# W102J.net
KiCad netlist of a schematic drawn in EAGLE
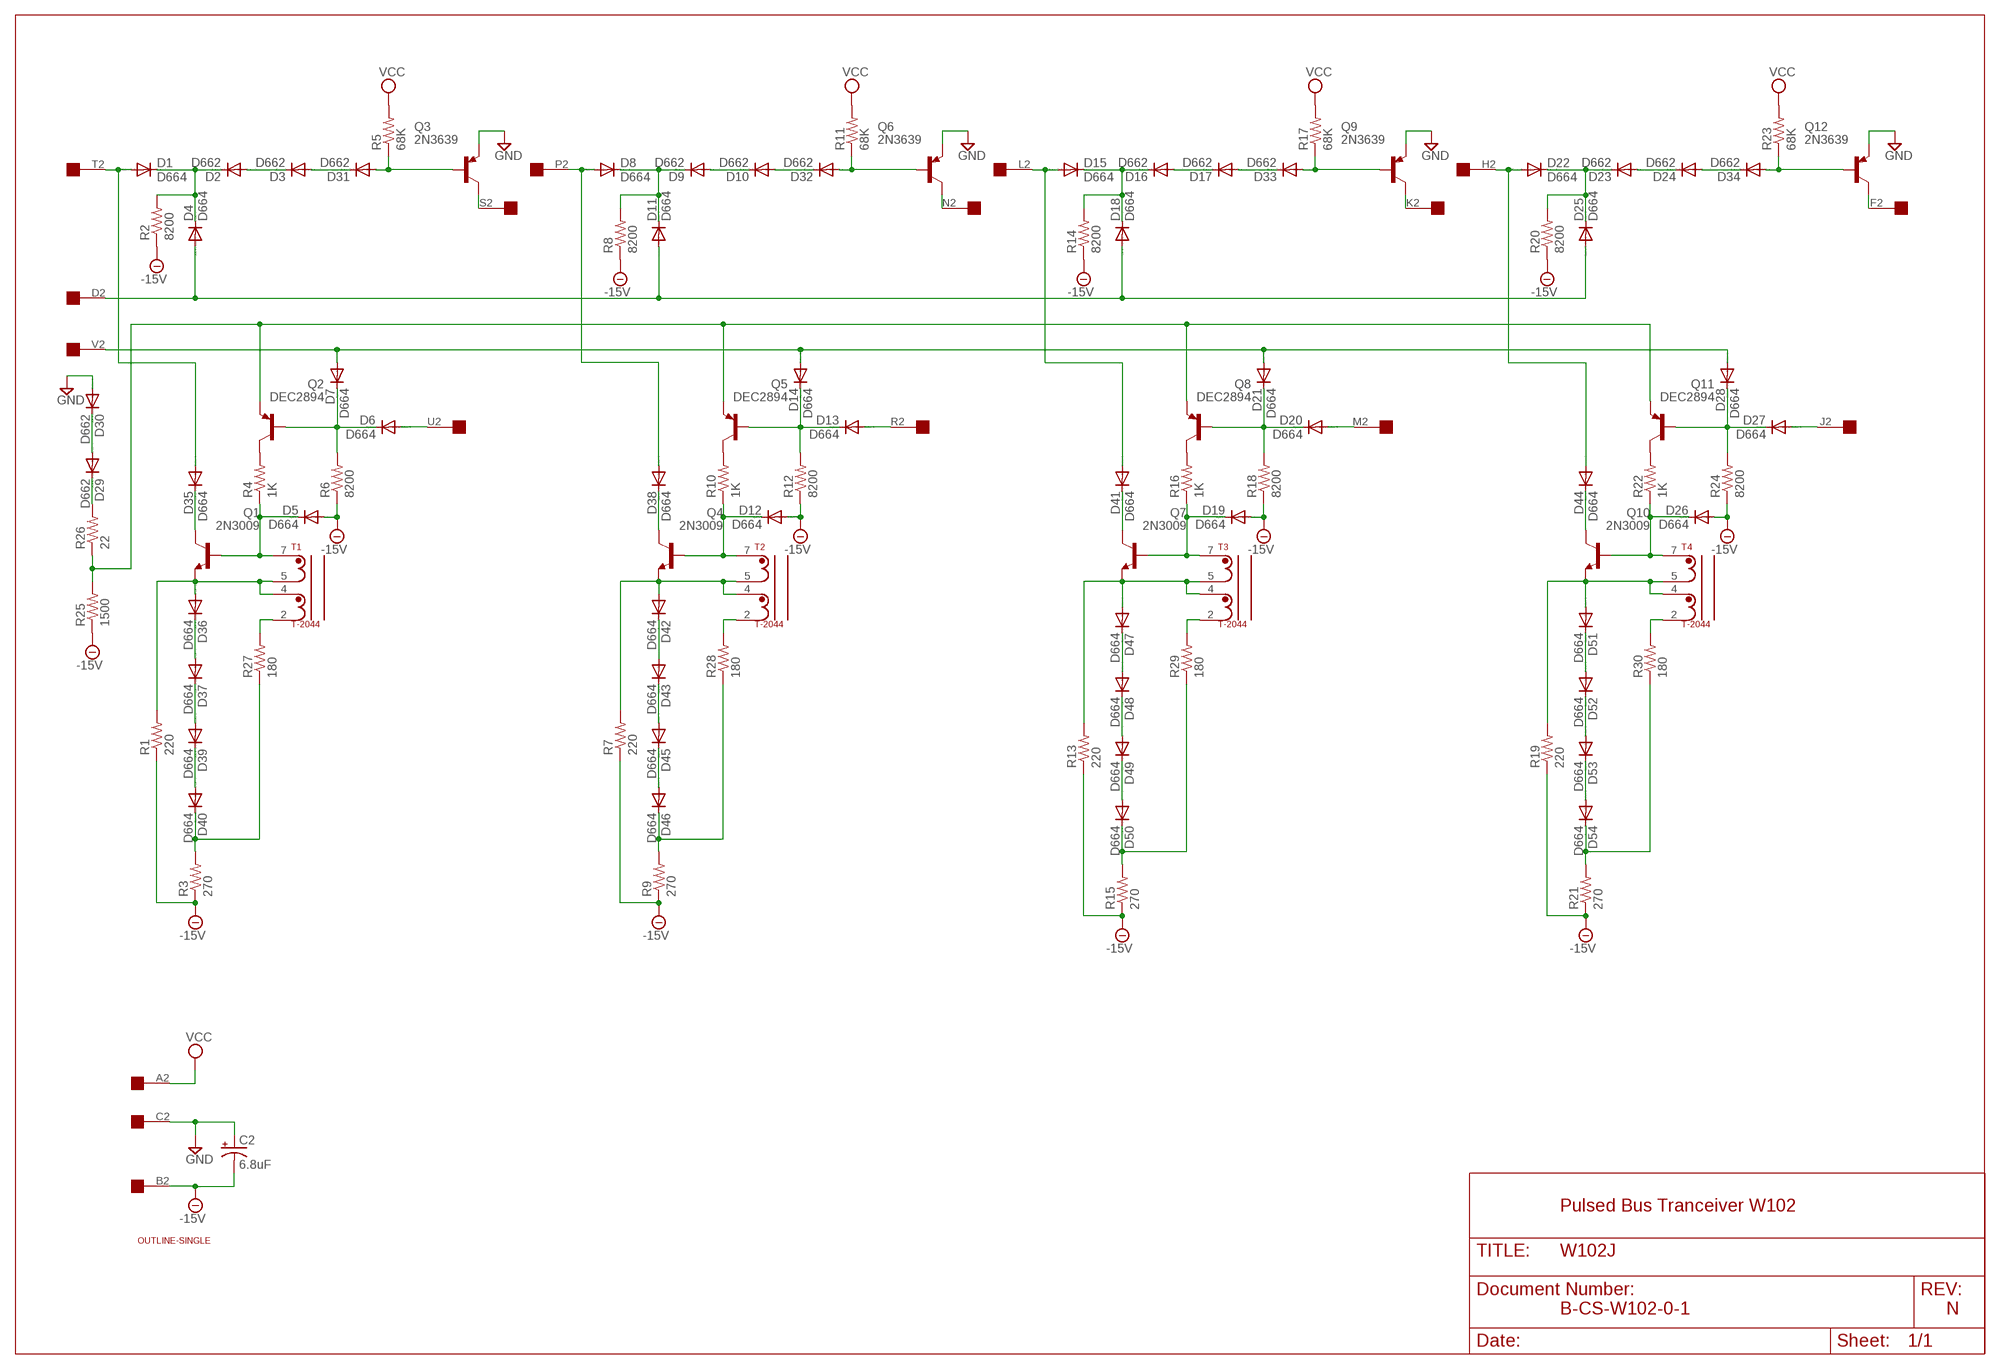
[diagram p0: schematic, sheet 1]

(export (version "E")
  (design (tool "Eeschema 10.0.6"))
  (components
    (comp (ref "C2")
      (value "6.8uF")
      (footprint "eagle-import:E15-5")
      (libsource (lib "eagle-import") (part "CPOL-USE15-5AXIAL"))
    )
    (comp (ref "D1")
      (value "D664")
      (footprint "eagle-import:DO35-10")
      (libsource (lib "eagle-import") (part "DIODE-DO35-10"))
    )
    (comp (ref "D2")
      (value "D662")
      (footprint "eagle-import:DO35-10")
      (libsource (lib "eagle-import") (part "DIODE-DO35-10"))
    )
    (comp (ref "D3")
      (value "D662")
      (footprint "eagle-import:DO35-10")
      (libsource (lib "eagle-import") (part "DIODE-DO35-10"))
    )
    (comp (ref "D4")
      (value "D664")
      (footprint "eagle-import:DO35-10")
      (libsource (lib "eagle-import") (part "DIODE-DO35-10"))
    )
    (comp (ref "D5")
      (value "D664")
      (footprint "eagle-import:DO35-10")
      (libsource (lib "eagle-import") (part "DIODE-DO35-10"))
    )
    (comp (ref "D6")
      (value "D664")
      (footprint "eagle-import:DO35-10")
      (libsource (lib "eagle-import") (part "DIODE-DO35-10"))
    )
    (comp (ref "D7")
      (value "D664")
      (footprint "eagle-import:DO35-10")
      (libsource (lib "eagle-import") (part "DIODE-DO35-10"))
    )
    (comp (ref "D8")
      (value "D664")
      (footprint "eagle-import:DO35-10")
      (libsource (lib "eagle-import") (part "DIODE-DO35-10"))
    )
    (comp (ref "D9")
      (value "D662")
      (footprint "eagle-import:DO35-10")
      (libsource (lib "eagle-import") (part "DIODE-DO35-10"))
    )
    (comp (ref "D10")
      (value "D662")
      (footprint "eagle-import:DO35-10")
      (libsource (lib "eagle-import") (part "DIODE-DO35-10"))
    )
    (comp (ref "D11")
      (value "D664")
      (footprint "eagle-import:DO35-10")
      (libsource (lib "eagle-import") (part "DIODE-DO35-10"))
    )
    (comp (ref "D12")
      (value "D664")
      (footprint "eagle-import:DO35-10")
      (libsource (lib "eagle-import") (part "DIODE-DO35-10"))
    )
    (comp (ref "D13")
      (value "D664")
      (footprint "eagle-import:DO35-10")
      (libsource (lib "eagle-import") (part "DIODE-DO35-10"))
    )
    (comp (ref "D14")
      (value "D664")
      (footprint "eagle-import:DO35-10")
      (libsource (lib "eagle-import") (part "DIODE-DO35-10"))
    )
    (comp (ref "D15")
      (value "D664")
      (footprint "eagle-import:DO35-10")
      (libsource (lib "eagle-import") (part "DIODE-DO35-10"))
    )
    (comp (ref "D16")
      (value "D662")
      (footprint "eagle-import:DO35-10")
      (libsource (lib "eagle-import") (part "DIODE-DO35-10"))
    )
    (comp (ref "D17")
      (value "D662")
      (footprint "eagle-import:DO35-10")
      (libsource (lib "eagle-import") (part "DIODE-DO35-10"))
    )
    (comp (ref "D18")
      (value "D664")
      (footprint "eagle-import:DO35-10")
      (libsource (lib "eagle-import") (part "DIODE-DO35-10"))
    )
    (comp (ref "D19")
      (value "D664")
      (footprint "eagle-import:DO35-10")
      (libsource (lib "eagle-import") (part "DIODE-DO35-10"))
    )
    (comp (ref "D20")
      (value "D664")
      (footprint "eagle-import:DO35-10")
      (libsource (lib "eagle-import") (part "DIODE-DO35-10"))
    )
    (comp (ref "D21")
      (value "D664")
      (footprint "eagle-import:DO35-10")
      (libsource (lib "eagle-import") (part "DIODE-DO35-10"))
    )
    (comp (ref "D22")
      (value "D664")
      (footprint "eagle-import:DO35-10")
      (libsource (lib "eagle-import") (part "DIODE-DO35-10"))
    )
    (comp (ref "D23")
      (value "D662")
      (footprint "eagle-import:DO35-10")
      (libsource (lib "eagle-import") (part "DIODE-DO35-10"))
    )
    (comp (ref "D24")
      (value "D662")
      (footprint "eagle-import:DO35-10")
      (libsource (lib "eagle-import") (part "DIODE-DO35-10"))
    )
    (comp (ref "D25")
      (value "D664")
      (footprint "eagle-import:DO35-10")
      (libsource (lib "eagle-import") (part "DIODE-DO35-10"))
    )
    (comp (ref "D26")
      (value "D664")
      (footprint "eagle-import:DO35-10")
      (libsource (lib "eagle-import") (part "DIODE-DO35-10"))
    )
    (comp (ref "D27")
      (value "D664")
      (footprint "eagle-import:DO35-10")
      (libsource (lib "eagle-import") (part "DIODE-DO35-10"))
    )
    (comp (ref "D28")
      (value "D664")
      (footprint "eagle-import:DO35-10")
      (libsource (lib "eagle-import") (part "DIODE-DO35-10"))
    )
    (comp (ref "D29")
      (value "D662")
      (footprint "eagle-import:DO35-10")
      (libsource (lib "eagle-import") (part "DIODE-DO35-10"))
    )
    (comp (ref "D30")
      (value "D662")
      (footprint "eagle-import:DO35-10")
      (libsource (lib "eagle-import") (part "DIODE-DO35-10"))
    )
    (comp (ref "D31")
      (value "D662")
      (footprint "eagle-import:DO35-10")
      (libsource (lib "eagle-import") (part "DIODE-DO35-10"))
    )
    (comp (ref "D32")
      (value "D662")
      (footprint "eagle-import:DO35-10")
      (libsource (lib "eagle-import") (part "DIODE-DO35-10"))
    )
    (comp (ref "D33")
      (value "D662")
      (footprint "eagle-import:DO35-10")
      (libsource (lib "eagle-import") (part "DIODE-DO35-10"))
    )
    (comp (ref "D34")
      (value "D662")
      (footprint "eagle-import:DO35-10")
      (libsource (lib "eagle-import") (part "DIODE-DO35-10"))
    )
    (comp (ref "D35")
      (value "D664")
      (footprint "eagle-import:DO35-10")
      (libsource (lib "eagle-import") (part "DIODE-DO35-10"))
    )
    (comp (ref "D36")
      (value "D664")
      (footprint "eagle-import:DO35-10")
      (libsource (lib "eagle-import") (part "DIODE-DO35-10"))
    )
    (comp (ref "D37")
      (value "D664")
      (footprint "eagle-import:DO35-10")
      (libsource (lib "eagle-import") (part "DIODE-DO35-10"))
    )
    (comp (ref "D38")
      (value "D664")
      (footprint "eagle-import:DO35-10")
      (libsource (lib "eagle-import") (part "DIODE-DO35-10"))
    )
    (comp (ref "D39")
      (value "D664")
      (footprint "eagle-import:DO35-10")
      (libsource (lib "eagle-import") (part "DIODE-DO35-10"))
    )
    (comp (ref "D40")
      (value "D664")
      (footprint "eagle-import:DO35-10")
      (libsource (lib "eagle-import") (part "DIODE-DO35-10"))
    )
    (comp (ref "D41")
      (value "D664")
      (footprint "eagle-import:DO35-10")
      (libsource (lib "eagle-import") (part "DIODE-DO35-10"))
    )
    (comp (ref "D42")
      (value "D664")
      (footprint "eagle-import:DO35-10")
      (libsource (lib "eagle-import") (part "DIODE-DO35-10"))
    )
    (comp (ref "D43")
      (value "D664")
      (footprint "eagle-import:DO35-10")
      (libsource (lib "eagle-import") (part "DIODE-DO35-10"))
    )
    (comp (ref "D44")
      (value "D664")
      (footprint "eagle-import:DO35-10")
      (libsource (lib "eagle-import") (part "DIODE-DO35-10"))
    )
    (comp (ref "D45")
      (value "D664")
      (footprint "eagle-import:DO35-10")
      (libsource (lib "eagle-import") (part "DIODE-DO35-10"))
    )
    (comp (ref "D46")
      (value "D664")
      (footprint "eagle-import:DO35-10")
      (libsource (lib "eagle-import") (part "DIODE-DO35-10"))
    )
    (comp (ref "D47")
      (value "D664")
      (footprint "eagle-import:DO35-10")
      (libsource (lib "eagle-import") (part "DIODE-DO35-10"))
    )
    (comp (ref "D48")
      (value "D664")
      (footprint "eagle-import:DO35-10")
      (libsource (lib "eagle-import") (part "DIODE-DO35-10"))
    )
    (comp (ref "D49")
      (value "D664")
      (footprint "eagle-import:DO35-10")
      (libsource (lib "eagle-import") (part "DIODE-DO35-10"))
    )
    (comp (ref "D50")
      (value "D664")
      (footprint "eagle-import:DO35-10")
      (libsource (lib "eagle-import") (part "DIODE-DO35-10"))
    )
    (comp (ref "D51")
      (value "D664")
      (footprint "eagle-import:DO35-10")
      (libsource (lib "eagle-import") (part "DIODE-DO35-10"))
    )
    (comp (ref "D52")
      (value "D664")
      (footprint "eagle-import:DO35-10")
      (libsource (lib "eagle-import") (part "DIODE-DO35-10"))
    )
    (comp (ref "D53")
      (value "D664")
      (footprint "eagle-import:DO35-10")
      (libsource (lib "eagle-import") (part "DIODE-DO35-10"))
    )
    (comp (ref "D54")
      (value "D664")
      (footprint "eagle-import:DO35-10")
      (libsource (lib "eagle-import") (part "DIODE-DO35-10"))
    )
    (comp (ref "Q1")
      (value "2N3009")
      (footprint "eagle-import:TO5")
      (libsource (lib "eagle-import") (part "-NPN-TO5"))
    )
    (comp (ref "Q2")
      (value "DEC2894")
      (footprint "eagle-import:TO5")
      (libsource (lib "eagle-import") (part "-PNP-TO5"))
    )
    (comp (ref "Q3")
      (value "2N3639")
      (footprint "eagle-import:TO5")
      (libsource (lib "eagle-import") (part "-PNP-TO5"))
    )
    (comp (ref "Q4")
      (value "2N3009")
      (footprint "eagle-import:TO5")
      (libsource (lib "eagle-import") (part "-NPN-TO5"))
    )
    (comp (ref "Q5")
      (value "DEC2894")
      (footprint "eagle-import:TO5")
      (libsource (lib "eagle-import") (part "-PNP-TO5"))
    )
    (comp (ref "Q6")
      (value "2N3639")
      (footprint "eagle-import:TO5")
      (libsource (lib "eagle-import") (part "-PNP-TO5"))
    )
    (comp (ref "Q7")
      (value "2N3009")
      (footprint "eagle-import:TO5")
      (libsource (lib "eagle-import") (part "-NPN-TO5"))
    )
    (comp (ref "Q8")
      (value "DEC2894")
      (footprint "eagle-import:TO5")
      (libsource (lib "eagle-import") (part "-PNP-TO5"))
    )
    (comp (ref "Q9")
      (value "2N3639")
      (footprint "eagle-import:TO5")
      (libsource (lib "eagle-import") (part "-PNP-TO5"))
    )
    (comp (ref "Q10")
      (value "2N3009")
      (footprint "eagle-import:TO5")
      (libsource (lib "eagle-import") (part "-NPN-TO5"))
    )
    (comp (ref "Q11")
      (value "DEC2894")
      (footprint "eagle-import:TO5")
      (libsource (lib "eagle-import") (part "-PNP-TO5"))
    )
    (comp (ref "Q12")
      (value "2N3639")
      (footprint "eagle-import:TO5")
      (libsource (lib "eagle-import") (part "-PNP-TO5"))
    )
    (comp (ref "R1")
      (value "220")
      (footprint "eagle-import:0207_10")
      (libsource (lib "eagle-import") (part "R-US_0207/10"))
    )
    (comp (ref "R2")
      (value "8200")
      (footprint "eagle-import:0207_10")
      (libsource (lib "eagle-import") (part "R-US_0207/10"))
    )
    (comp (ref "R3")
      (value "270")
      (footprint "eagle-import:0207_10")
      (libsource (lib "eagle-import") (part "R-US_0207/10"))
    )
    (comp (ref "R4")
      (value "1K")
      (footprint "eagle-import:0207_10")
      (libsource (lib "eagle-import") (part "R-US_0207/10"))
    )
    (comp (ref "R5")
      (value "68K")
      (footprint "eagle-import:0207_10")
      (libsource (lib "eagle-import") (part "R-US_0207/10"))
    )
    (comp (ref "R6")
      (value "8200")
      (footprint "eagle-import:0207_10")
      (libsource (lib "eagle-import") (part "R-US_0207/10"))
    )
    (comp (ref "R7")
      (value "220")
      (footprint "eagle-import:0207_10")
      (libsource (lib "eagle-import") (part "R-US_0207/10"))
    )
    (comp (ref "R8")
      (value "8200")
      (footprint "eagle-import:0207_10")
      (libsource (lib "eagle-import") (part "R-US_0207/10"))
    )
    (comp (ref "R9")
      (value "270")
      (footprint "eagle-import:0207_10")
      (libsource (lib "eagle-import") (part "R-US_0207/10"))
    )
    (comp (ref "R10")
      (value "1K")
      (footprint "eagle-import:0207_10")
      (libsource (lib "eagle-import") (part "R-US_0207/10"))
    )
    (comp (ref "R11")
      (value "68K")
      (footprint "eagle-import:0207_10")
      (libsource (lib "eagle-import") (part "R-US_0207/10"))
    )
    (comp (ref "R12")
      (value "8200")
      (footprint "eagle-import:0207_10")
      (libsource (lib "eagle-import") (part "R-US_0207/10"))
    )
    (comp (ref "R13")
      (value "220")
      (footprint "eagle-import:0207_10")
      (libsource (lib "eagle-import") (part "R-US_0207/10"))
    )
    (comp (ref "R14")
      (value "8200")
      (footprint "eagle-import:0207_10")
      (libsource (lib "eagle-import") (part "R-US_0207/10"))
    )
    (comp (ref "R15")
      (value "270")
      (footprint "eagle-import:0207_10")
      (libsource (lib "eagle-import") (part "R-US_0207/10"))
    )
    (comp (ref "R16")
      (value "1K")
      (footprint "eagle-import:0207_10")
      (libsource (lib "eagle-import") (part "R-US_0207/10"))
    )
    (comp (ref "R17")
      (value "68K")
      (footprint "eagle-import:0207_10")
      (libsource (lib "eagle-import") (part "R-US_0207/10"))
    )
    (comp (ref "R18")
      (value "8200")
      (footprint "eagle-import:0207_10")
      (libsource (lib "eagle-import") (part "R-US_0207/10"))
    )
    (comp (ref "R19")
      (value "220")
      (footprint "eagle-import:0207_10")
      (libsource (lib "eagle-import") (part "R-US_0207/10"))
    )
    (comp (ref "R20")
      (value "8200")
      (footprint "eagle-import:0207_10")
      (libsource (lib "eagle-import") (part "R-US_0207/10"))
    )
    (comp (ref "R21")
      (value "270")
      (footprint "eagle-import:0207_10")
      (libsource (lib "eagle-import") (part "R-US_0207/10"))
    )
    (comp (ref "R22")
      (value "1K")
      (footprint "eagle-import:0207_10")
      (libsource (lib "eagle-import") (part "R-US_0207/10"))
    )
    (comp (ref "R23")
      (value "68K")
      (footprint "eagle-import:0207_10")
      (libsource (lib "eagle-import") (part "R-US_0207/10"))
    )
    (comp (ref "R24")
      (value "8200")
      (footprint "eagle-import:0207_10")
      (libsource (lib "eagle-import") (part "R-US_0207/10"))
    )
    (comp (ref "R25")
      (value "1500")
      (footprint "eagle-import:0207_10")
      (libsource (lib "eagle-import") (part "R-US_0207/10"))
    )
    (comp (ref "R26")
      (value "22")
      (footprint "eagle-import:0207_10")
      (libsource (lib "eagle-import") (part "R-US_0207/10"))
    )
    (comp (ref "R27")
      (value "180")
      (footprint "eagle-import:0207_10")
      (libsource (lib "eagle-import") (part "R-US_0207/10"))
    )
    (comp (ref "R28")
      (value "180")
      (footprint "eagle-import:0207_10")
      (libsource (lib "eagle-import") (part "R-US_0207/10"))
    )
    (comp (ref "R29")
      (value "180")
      (footprint "eagle-import:0207_10")
      (libsource (lib "eagle-import") (part "R-US_0207/10"))
    )
    (comp (ref "R30")
      (value "180")
      (footprint "eagle-import:0207_10")
      (libsource (lib "eagle-import") (part "R-US_0207/10"))
    )
    (comp (ref "T1")
      (value "T-2044")
      (footprint "eagle-import:TRANSFORMER")
      (libsource (lib "eagle-import") (part "T-2044"))
    )
    (comp (ref "T2")
      (value "T-2044")
      (footprint "eagle-import:TRANSFORMER")
      (libsource (lib "eagle-import") (part "T-2044"))
    )
    (comp (ref "T3")
      (value "T-2044")
      (footprint "eagle-import:TRANSFORMER")
      (libsource (lib "eagle-import") (part "T-2044"))
    )
    (comp (ref "T4")
      (value "T-2044")
      (footprint "eagle-import:TRANSFORMER")
      (libsource (lib "eagle-import") (part "T-2044"))
    )
    (comp (ref "U$1")
      (value "OUTLINE-SINGLE")
      (footprint "eagle-import:SINGLE")
      (libsource (lib "eagle-import") (part "OUTLINE-SINGLE"))
    )
    (comp (ref "U$2")
      (value "EDGE-1")
      (footprint "eagle-import:EDGE-CON1")
      (libsource (lib "eagle-import") (part "EDGE-1"))
    )
  )
  (nets
    (net (code "1") (name "-15V") (class "Default")
      (node (ref "C2") (pin "-") (pinfunction "-_-") (pintype "passive"))
      (node (ref "D12") (pin "A") (pinfunction "A_A") (pintype "passive"))
      (node (ref "D19") (pin "A") (pinfunction "A_A") (pintype "passive"))
      (node (ref "D26") (pin "A") (pinfunction "A_A") (pintype "passive"))
      (node (ref "D5") (pin "A") (pinfunction "A_A") (pintype "passive"))
      (node (ref "R1") (pin "1") (pinfunction "1_1") (pintype "passive"))
      (node (ref "R12") (pin "1") (pinfunction "1_1") (pintype "passive"))
      (node (ref "R13") (pin "1") (pinfunction "1_1") (pintype "passive"))
      (node (ref "R14") (pin "1") (pinfunction "1_1") (pintype "passive"))
      (node (ref "R15") (pin "1") (pinfunction "1_1") (pintype "passive"))
      (node (ref "R18") (pin "1") (pinfunction "1_1") (pintype "passive"))
      (node (ref "R19") (pin "1") (pinfunction "1_1") (pintype "passive"))
      (node (ref "R2") (pin "1") (pinfunction "1_1") (pintype "passive"))
      (node (ref "R20") (pin "1") (pinfunction "1_1") (pintype "passive"))
      (node (ref "R21") (pin "1") (pinfunction "1_1") (pintype "passive"))
      (node (ref "R24") (pin "1") (pinfunction "1_1") (pintype "passive"))
      (node (ref "R25") (pin "1") (pinfunction "1_1") (pintype "passive"))
      (node (ref "R3") (pin "1") (pinfunction "1_1") (pintype "passive"))
      (node (ref "R6") (pin "1") (pinfunction "1_1") (pintype "passive"))
      (node (ref "R7") (pin "1") (pinfunction "1_1") (pintype "passive"))
      (node (ref "R8") (pin "1") (pinfunction "1_1") (pintype "passive"))
      (node (ref "R9") (pin "1") (pinfunction "1_1") (pintype "passive"))
      (node (ref "U$2") (pin "B2") (pinfunction "1_B2") (pintype "bidirectional"))
    )
    (net (code "2") (name "GND") (class "Default")
      (node (ref "C2") (pin "+") (pinfunction "+_+") (pintype "passive"))
      (node (ref "D30") (pin "A") (pinfunction "A_A") (pintype "passive"))
      (node (ref "Q12") (pin "1") (pinfunction "E_1") (pintype "passive"))
      (node (ref "Q3") (pin "1") (pinfunction "E_1") (pintype "passive"))
      (node (ref "Q6") (pin "1") (pinfunction "E_1") (pintype "passive"))
      (node (ref "Q9") (pin "1") (pinfunction "E_1") (pintype "passive"))
      (node (ref "U$2") (pin "C2") (pinfunction "1_C2") (pintype "bidirectional"))
    )
    (net (code "3") (name "Net-(D1-PadC)") (class "Default")
      (node (ref "D1") (pin "C") (pinfunction "C_C") (pintype "passive"))
      (node (ref "D2") (pin "C") (pinfunction "C_C") (pintype "passive"))
      (node (ref "D4") (pin "C") (pinfunction "C_C") (pintype "passive"))
      (node (ref "R2") (pin "2") (pinfunction "2_2") (pintype "passive"))
    )
    (net (code "4") (name "Net-(D2-PadA)") (class "Default")
      (node (ref "D2") (pin "A") (pinfunction "A_A") (pintype "passive"))
      (node (ref "D3") (pin "C") (pinfunction "C_C") (pintype "passive"))
    )
    (net (code "5") (name "Net-(D3-PadA)") (class "Default")
      (node (ref "D3") (pin "A") (pinfunction "A_A") (pintype "passive"))
      (node (ref "D31") (pin "C") (pinfunction "C_C") (pintype "passive"))
    )
    (net (code "6") (name "Net-(D10-PadA)") (class "Default")
      (node (ref "D10") (pin "A") (pinfunction "A_A") (pintype "passive"))
      (node (ref "D32") (pin "C") (pinfunction "C_C") (pintype "passive"))
    )
    (net (code "7") (name "Net-(D10-PadC)") (class "Default")
      (node (ref "D10") (pin "C") (pinfunction "C_C") (pintype "passive"))
      (node (ref "D9") (pin "A") (pinfunction "A_A") (pintype "passive"))
    )
    (net (code "8") (name "Net-(D11-PadC)") (class "Default")
      (node (ref "D11") (pin "C") (pinfunction "C_C") (pintype "passive"))
      (node (ref "D8") (pin "C") (pinfunction "C_C") (pintype "passive"))
      (node (ref "D9") (pin "C") (pinfunction "C_C") (pintype "passive"))
      (node (ref "R8") (pin "2") (pinfunction "2_2") (pintype "passive"))
    )
    (net (code "9") (name "Net-(D15-PadC)") (class "Default")
      (node (ref "D15") (pin "C") (pinfunction "C_C") (pintype "passive"))
      (node (ref "D16") (pin "C") (pinfunction "C_C") (pintype "passive"))
      (node (ref "D18") (pin "C") (pinfunction "C_C") (pintype "passive"))
      (node (ref "R14") (pin "2") (pinfunction "2_2") (pintype "passive"))
    )
    (net (code "10") (name "Net-(D16-PadA)") (class "Default")
      (node (ref "D16") (pin "A") (pinfunction "A_A") (pintype "passive"))
      (node (ref "D17") (pin "C") (pinfunction "C_C") (pintype "passive"))
    )
    (net (code "11") (name "Net-(D17-PadA)") (class "Default")
      (node (ref "D17") (pin "A") (pinfunction "A_A") (pintype "passive"))
      (node (ref "D33") (pin "C") (pinfunction "C_C") (pintype "passive"))
    )
    (net (code "12") (name "Net-(D22-PadC)") (class "Default")
      (node (ref "D22") (pin "C") (pinfunction "C_C") (pintype "passive"))
      (node (ref "D23") (pin "C") (pinfunction "C_C") (pintype "passive"))
      (node (ref "D25") (pin "C") (pinfunction "C_C") (pintype "passive"))
      (node (ref "R20") (pin "2") (pinfunction "2_2") (pintype "passive"))
    )
    (net (code "13") (name "Net-(D23-PadA)") (class "Default")
      (node (ref "D23") (pin "A") (pinfunction "A_A") (pintype "passive"))
      (node (ref "D24") (pin "C") (pinfunction "C_C") (pintype "passive"))
    )
    (net (code "14") (name "Net-(D24-PadA)") (class "Default")
      (node (ref "D24") (pin "A") (pinfunction "A_A") (pintype "passive"))
      (node (ref "D34") (pin "C") (pinfunction "C_C") (pintype "passive"))
    )
    (net (code "15") (name "Net-(D29-PadA)") (class "Default")
      (node (ref "D29") (pin "A") (pinfunction "A_A") (pintype "passive"))
      (node (ref "D30") (pin "C") (pinfunction "C_C") (pintype "passive"))
    )
    (net (code "16") (name "Net-(D29-PadC)") (class "Default")
      (node (ref "D29") (pin "C") (pinfunction "C_C") (pintype "passive"))
      (node (ref "R26") (pin "2") (pinfunction "2_2") (pintype "passive"))
    )
    (net (code "17") (name "Net-(D36-PadC)") (class "Default")
      (node (ref "D36") (pin "C") (pinfunction "C_C") (pintype "passive"))
      (node (ref "D37") (pin "A") (pinfunction "A_A") (pintype "passive"))
    )
    (net (code "18") (name "Net-(D37-PadC)") (class "Default")
      (node (ref "D37") (pin "C") (pinfunction "C_C") (pintype "passive"))
      (node (ref "D39") (pin "A") (pinfunction "A_A") (pintype "passive"))
    )
    (net (code "19") (name "Net-(D39-PadC)") (class "Default")
      (node (ref "D39") (pin "C") (pinfunction "C_C") (pintype "passive"))
      (node (ref "D40") (pin "A") (pinfunction "A_A") (pintype "passive"))
    )
    (net (code "20") (name "Net-(D40-PadC)") (class "Default")
      (node (ref "D40") (pin "C") (pinfunction "C_C") (pintype "passive"))
      (node (ref "R27") (pin "1") (pinfunction "1_1") (pintype "passive"))
      (node (ref "R3") (pin "2") (pinfunction "2_2") (pintype "passive"))
    )
    (net (code "21") (name "Net-(D42-PadC)") (class "Default")
      (node (ref "D42") (pin "C") (pinfunction "C_C") (pintype "passive"))
      (node (ref "D43") (pin "A") (pinfunction "A_A") (pintype "passive"))
    )
    (net (code "22") (name "Net-(D43-PadC)") (class "Default")
      (node (ref "D43") (pin "C") (pinfunction "C_C") (pintype "passive"))
      (node (ref "D45") (pin "A") (pinfunction "A_A") (pintype "passive"))
    )
    (net (code "23") (name "Net-(D45-PadC)") (class "Default")
      (node (ref "D45") (pin "C") (pinfunction "C_C") (pintype "passive"))
      (node (ref "D46") (pin "A") (pinfunction "A_A") (pintype "passive"))
    )
    (net (code "24") (name "Net-(D46-PadC)") (class "Default")
      (node (ref "D46") (pin "C") (pinfunction "C_C") (pintype "passive"))
      (node (ref "R28") (pin "1") (pinfunction "1_1") (pintype "passive"))
      (node (ref "R9") (pin "2") (pinfunction "2_2") (pintype "passive"))
    )
    (net (code "25") (name "Net-(D47-PadC)") (class "Default")
      (node (ref "D47") (pin "C") (pinfunction "C_C") (pintype "passive"))
      (node (ref "D48") (pin "A") (pinfunction "A_A") (pintype "passive"))
    )
    (net (code "26") (name "Net-(D48-PadC)") (class "Default")
      (node (ref "D48") (pin "C") (pinfunction "C_C") (pintype "passive"))
      (node (ref "D49") (pin "A") (pinfunction "A_A") (pintype "passive"))
    )
    (net (code "27") (name "Net-(D49-PadC)") (class "Default")
      (node (ref "D49") (pin "C") (pinfunction "C_C") (pintype "passive"))
      (node (ref "D50") (pin "A") (pinfunction "A_A") (pintype "passive"))
    )
    (net (code "28") (name "Net-(D50-PadC)") (class "Default")
      (node (ref "D50") (pin "C") (pinfunction "C_C") (pintype "passive"))
      (node (ref "R15") (pin "2") (pinfunction "2_2") (pintype "passive"))
      (node (ref "R29") (pin "1") (pinfunction "1_1") (pintype "passive"))
    )
    (net (code "29") (name "Net-(D51-PadC)") (class "Default")
      (node (ref "D51") (pin "C") (pinfunction "C_C") (pintype "passive"))
      (node (ref "D52") (pin "A") (pinfunction "A_A") (pintype "passive"))
    )
    (net (code "30") (name "Net-(D52-PadC)") (class "Default")
      (node (ref "D52") (pin "C") (pinfunction "C_C") (pintype "passive"))
      (node (ref "D53") (pin "A") (pinfunction "A_A") (pintype "passive"))
    )
    (net (code "31") (name "Net-(D53-PadC)") (class "Default")
      (node (ref "D53") (pin "C") (pinfunction "C_C") (pintype "passive"))
      (node (ref "D54") (pin "A") (pinfunction "A_A") (pintype "passive"))
    )
    (net (code "32") (name "Net-(D54-PadC)") (class "Default")
      (node (ref "D54") (pin "C") (pinfunction "C_C") (pintype "passive"))
      (node (ref "R21") (pin "2") (pinfunction "2_2") (pintype "passive"))
      (node (ref "R30") (pin "1") (pinfunction "1_1") (pintype "passive"))
    )
    (net (code "33") (name "Net-(Q1-B)") (class "Default")
      (node (ref "D5") (pin "C") (pinfunction "C_C") (pintype "passive"))
      (node (ref "Q1") (pin "2") (pinfunction "B_2") (pintype "passive"))
      (node (ref "R4") (pin "1") (pinfunction "1_1") (pintype "passive"))
      (node (ref "T1") (pin "7") (pinfunction "2_7") (pintype "passive"))
    )
    (net (code "34") (name "Net-(Q1-C)") (class "Default")
      (node (ref "D35") (pin "C") (pinfunction "C_C") (pintype "passive"))
      (node (ref "Q1") (pin "3") (pinfunction "C_3") (pintype "passive"))
    )
    (net (code "35") (name "Net-(Q1-E)") (class "Default")
      (node (ref "D36") (pin "A") (pinfunction "A_A") (pintype "passive"))
      (node (ref "Q1") (pin "1") (pinfunction "E_1") (pintype "passive"))
      (node (ref "R1") (pin "2") (pinfunction "2_2") (pintype "passive"))
      (node (ref "T1") (pin "4") (pinfunction "1_4") (pintype "passive"))
      (node (ref "T1") (pin "5") (pinfunction "5_5") (pintype "passive"))
    )
    (net (code "36") (name "Net-(Q2-B)") (class "Default")
      (node (ref "D6") (pin "C") (pinfunction "C_C") (pintype "passive"))
      (node (ref "D7") (pin "C") (pinfunction "C_C") (pintype "passive"))
      (node (ref "Q2") (pin "2") (pinfunction "B_2") (pintype "passive"))
      (node (ref "R6") (pin "2") (pinfunction "2_2") (pintype "passive"))
    )
    (net (code "37") (name "Net-(Q2-C)") (class "Default")
      (node (ref "Q2") (pin "3") (pinfunction "C_3") (pintype "passive"))
      (node (ref "R4") (pin "2") (pinfunction "2_2") (pintype "passive"))
    )
    (net (code "38") (name "Net-(Q3-B)") (class "Default")
      (node (ref "D31") (pin "A") (pinfunction "A_A") (pintype "passive"))
      (node (ref "Q3") (pin "2") (pinfunction "B_2") (pintype "passive"))
      (node (ref "R5") (pin "1") (pinfunction "1_1") (pintype "passive"))
    )
    (net (code "39") (name "Net-(Q3-C)") (class "Default")
      (node (ref "Q3") (pin "3") (pinfunction "C_3") (pintype "passive"))
      (node (ref "U$2") (pin "S2") (pinfunction "1_S2") (pintype "bidirectional"))
    )
    (net (code "40") (name "Net-(Q4-B)") (class "Default")
      (node (ref "D12") (pin "C") (pinfunction "C_C") (pintype "passive"))
      (node (ref "Q4") (pin "2") (pinfunction "B_2") (pintype "passive"))
      (node (ref "R10") (pin "1") (pinfunction "1_1") (pintype "passive"))
      (node (ref "T2") (pin "7") (pinfunction "2_7") (pintype "passive"))
    )
    (net (code "41") (name "Net-(Q4-C)") (class "Default")
      (node (ref "D38") (pin "C") (pinfunction "C_C") (pintype "passive"))
      (node (ref "Q4") (pin "3") (pinfunction "C_3") (pintype "passive"))
    )
    (net (code "42") (name "Net-(Q4-E)") (class "Default")
      (node (ref "D42") (pin "A") (pinfunction "A_A") (pintype "passive"))
      (node (ref "Q4") (pin "1") (pinfunction "E_1") (pintype "passive"))
      (node (ref "R7") (pin "2") (pinfunction "2_2") (pintype "passive"))
      (node (ref "T2") (pin "4") (pinfunction "1_4") (pintype "passive"))
      (node (ref "T2") (pin "5") (pinfunction "5_5") (pintype "passive"))
    )
    (net (code "43") (name "Net-(Q5-B)") (class "Default")
      (node (ref "D13") (pin "C") (pinfunction "C_C") (pintype "passive"))
      (node (ref "D14") (pin "C") (pinfunction "C_C") (pintype "passive"))
      (node (ref "Q5") (pin "2") (pinfunction "B_2") (pintype "passive"))
      (node (ref "R12") (pin "2") (pinfunction "2_2") (pintype "passive"))
    )
    (net (code "44") (name "Net-(Q5-C)") (class "Default")
      (node (ref "Q5") (pin "3") (pinfunction "C_3") (pintype "passive"))
      (node (ref "R10") (pin "2") (pinfunction "2_2") (pintype "passive"))
    )
    (net (code "45") (name "Net-(Q6-B)") (class "Default")
      (node (ref "D32") (pin "A") (pinfunction "A_A") (pintype "passive"))
      (node (ref "Q6") (pin "2") (pinfunction "B_2") (pintype "passive"))
      (node (ref "R11") (pin "1") (pinfunction "1_1") (pintype "passive"))
    )
    (net (code "46") (name "Net-(Q6-C)") (class "Default")
      (node (ref "Q6") (pin "3") (pinfunction "C_3") (pintype "passive"))
      (node (ref "U$2") (pin "N2") (pinfunction "1_N2") (pintype "bidirectional"))
    )
    (net (code "47") (name "Net-(Q7-B)") (class "Default")
      (node (ref "D19") (pin "C") (pinfunction "C_C") (pintype "passive"))
      (node (ref "Q7") (pin "2") (pinfunction "B_2") (pintype "passive"))
      (node (ref "R16") (pin "1") (pinfunction "1_1") (pintype "passive"))
      (node (ref "T3") (pin "7") (pinfunction "2_7") (pintype "passive"))
    )
    (net (code "48") (name "Net-(Q7-C)") (class "Default")
      (node (ref "D41") (pin "C") (pinfunction "C_C") (pintype "passive"))
      (node (ref "Q7") (pin "3") (pinfunction "C_3") (pintype "passive"))
    )
    (net (code "49") (name "Net-(Q7-E)") (class "Default")
      (node (ref "D47") (pin "A") (pinfunction "A_A") (pintype "passive"))
      (node (ref "Q7") (pin "1") (pinfunction "E_1") (pintype "passive"))
      (node (ref "R13") (pin "2") (pinfunction "2_2") (pintype "passive"))
      (node (ref "T3") (pin "4") (pinfunction "1_4") (pintype "passive"))
      (node (ref "T3") (pin "5") (pinfunction "5_5") (pintype "passive"))
    )
    (net (code "50") (name "Net-(Q8-B)") (class "Default")
      (node (ref "D20") (pin "C") (pinfunction "C_C") (pintype "passive"))
      (node (ref "D21") (pin "C") (pinfunction "C_C") (pintype "passive"))
      (node (ref "Q8") (pin "2") (pinfunction "B_2") (pintype "passive"))
      (node (ref "R18") (pin "2") (pinfunction "2_2") (pintype "passive"))
    )
    (net (code "51") (name "Net-(Q8-C)") (class "Default")
      (node (ref "Q8") (pin "3") (pinfunction "C_3") (pintype "passive"))
      (node (ref "R16") (pin "2") (pinfunction "2_2") (pintype "passive"))
    )
    (net (code "52") (name "Net-(Q9-B)") (class "Default")
      (node (ref "D33") (pin "A") (pinfunction "A_A") (pintype "passive"))
      (node (ref "Q9") (pin "2") (pinfunction "B_2") (pintype "passive"))
      (node (ref "R17") (pin "1") (pinfunction "1_1") (pintype "passive"))
    )
    (net (code "53") (name "Net-(Q9-C)") (class "Default")
      (node (ref "Q9") (pin "3") (pinfunction "C_3") (pintype "passive"))
      (node (ref "U$2") (pin "K2") (pinfunction "1_K2") (pintype "bidirectional"))
    )
    (net (code "54") (name "Net-(Q10-B)") (class "Default")
      (node (ref "D26") (pin "C") (pinfunction "C_C") (pintype "passive"))
      (node (ref "Q10") (pin "2") (pinfunction "B_2") (pintype "passive"))
      (node (ref "R22") (pin "1") (pinfunction "1_1") (pintype "passive"))
      (node (ref "T4") (pin "7") (pinfunction "2_7") (pintype "passive"))
    )
    (net (code "55") (name "Net-(Q10-C)") (class "Default")
      (node (ref "D44") (pin "C") (pinfunction "C_C") (pintype "passive"))
      (node (ref "Q10") (pin "3") (pinfunction "C_3") (pintype "passive"))
    )
    (net (code "56") (name "Net-(Q10-E)") (class "Default")
      (node (ref "D51") (pin "A") (pinfunction "A_A") (pintype "passive"))
      (node (ref "Q10") (pin "1") (pinfunction "E_1") (pintype "passive"))
      (node (ref "R19") (pin "2") (pinfunction "2_2") (pintype "passive"))
      (node (ref "T4") (pin "4") (pinfunction "1_4") (pintype "passive"))
      (node (ref "T4") (pin "5") (pinfunction "5_5") (pintype "passive"))
    )
    (net (code "57") (name "Net-(Q11-B)") (class "Default")
      (node (ref "D27") (pin "C") (pinfunction "C_C") (pintype "passive"))
      (node (ref "D28") (pin "C") (pinfunction "C_C") (pintype "passive"))
      (node (ref "Q11") (pin "2") (pinfunction "B_2") (pintype "passive"))
      (node (ref "R24") (pin "2") (pinfunction "2_2") (pintype "passive"))
    )
    (net (code "58") (name "Net-(Q11-C)") (class "Default")
      (node (ref "Q11") (pin "3") (pinfunction "C_3") (pintype "passive"))
      (node (ref "R22") (pin "2") (pinfunction "2_2") (pintype "passive"))
    )
    (net (code "59") (name "Net-(Q11-E)") (class "Default")
      (node (ref "Q11") (pin "1") (pinfunction "E_1") (pintype "passive"))
      (node (ref "Q2") (pin "1") (pinfunction "E_1") (pintype "passive"))
      (node (ref "Q5") (pin "1") (pinfunction "E_1") (pintype "passive"))
      (node (ref "Q8") (pin "1") (pinfunction "E_1") (pintype "passive"))
      (node (ref "R25") (pin "2") (pinfunction "2_2") (pintype "passive"))
      (node (ref "R26") (pin "1") (pinfunction "1_1") (pintype "passive"))
    )
    (net (code "60") (name "Net-(Q12-B)") (class "Default")
      (node (ref "D34") (pin "A") (pinfunction "A_A") (pintype "passive"))
      (node (ref "Q12") (pin "2") (pinfunction "B_2") (pintype "passive"))
      (node (ref "R23") (pin "1") (pinfunction "1_1") (pintype "passive"))
    )
    (net (code "61") (name "Net-(Q12-C)") (class "Default")
      (node (ref "Q12") (pin "3") (pinfunction "C_3") (pintype "passive"))
      (node (ref "U$2") (pin "F2") (pinfunction "1_F2") (pintype "bidirectional"))
    )
    (net (code "62") (name "Net-(T1-6)") (class "Default")
      (node (ref "R27") (pin "2") (pinfunction "2_2") (pintype "passive"))
      (node (ref "T1") (pin "2") (pinfunction "6_2") (pintype "passive"))
    )
    (net (code "63") (name "Net-(T2-6)") (class "Default")
      (node (ref "R28") (pin "2") (pinfunction "2_2") (pintype "passive"))
      (node (ref "T2") (pin "2") (pinfunction "6_2") (pintype "passive"))
    )
    (net (code "64") (name "Net-(T3-6)") (class "Default")
      (node (ref "R29") (pin "2") (pinfunction "2_2") (pintype "passive"))
      (node (ref "T3") (pin "2") (pinfunction "6_2") (pintype "passive"))
    )
    (net (code "65") (name "Net-(T4-6)") (class "Default")
      (node (ref "R30") (pin "2") (pinfunction "2_2") (pintype "passive"))
      (node (ref "T4") (pin "2") (pinfunction "6_2") (pintype "passive"))
    )
    (net (code "66") (name "Net-(U$2D-1)") (class "Default")
      (node (ref "D11") (pin "A") (pinfunction "A_A") (pintype "passive"))
      (node (ref "D18") (pin "A") (pinfunction "A_A") (pintype "passive"))
      (node (ref "D25") (pin "A") (pinfunction "A_A") (pintype "passive"))
      (node (ref "D4") (pin "A") (pinfunction "A_A") (pintype "passive"))
      (node (ref "U$2") (pin "D2") (pinfunction "1_D2") (pintype "bidirectional"))
    )
    (net (code "67") (name "Net-(U$2G-1)") (class "Default")
      (node (ref "D22") (pin "A") (pinfunction "A_A") (pintype "passive"))
      (node (ref "D44") (pin "A") (pinfunction "A_A") (pintype "passive"))
      (node (ref "U$2") (pin "H2") (pinfunction "1_H2") (pintype "bidirectional"))
    )
    (net (code "68") (name "Net-(U$2H-1)") (class "Default")
      (node (ref "D27") (pin "A") (pinfunction "A_A") (pintype "passive"))
      (node (ref "U$2") (pin "J2") (pinfunction "1_J2") (pintype "bidirectional"))
    )
    (net (code "69") (name "Net-(U$2J-1)") (class "Default")
      (node (ref "D15") (pin "A") (pinfunction "A_A") (pintype "passive"))
      (node (ref "D41") (pin "A") (pinfunction "A_A") (pintype "passive"))
      (node (ref "U$2") (pin "L2") (pinfunction "1_L2") (pintype "bidirectional"))
    )
    (net (code "70") (name "Net-(U$2K-1)") (class "Default")
      (node (ref "D20") (pin "A") (pinfunction "A_A") (pintype "passive"))
      (node (ref "U$2") (pin "M2") (pinfunction "1_M2") (pintype "bidirectional"))
    )
    (net (code "71") (name "Net-(U$2M-1)") (class "Default")
      (node (ref "D38") (pin "A") (pinfunction "A_A") (pintype "passive"))
      (node (ref "D8") (pin "A") (pinfunction "A_A") (pintype "passive"))
      (node (ref "U$2") (pin "P2") (pinfunction "1_P2") (pintype "bidirectional"))
    )
    (net (code "72") (name "Net-(U$2N-1)") (class "Default")
      (node (ref "D13") (pin "A") (pinfunction "A_A") (pintype "passive"))
      (node (ref "U$2") (pin "R2") (pinfunction "1_R2") (pintype "bidirectional"))
    )
    (net (code "73") (name "Net-(U$2P-1)") (class "Default")
      (node (ref "D1") (pin "A") (pinfunction "A_A") (pintype "passive"))
      (node (ref "D35") (pin "A") (pinfunction "A_A") (pintype "passive"))
      (node (ref "U$2") (pin "T2") (pinfunction "1_T2") (pintype "bidirectional"))
    )
    (net (code "74") (name "Net-(U$2Q-1)") (class "Default")
      (node (ref "D6") (pin "A") (pinfunction "A_A") (pintype "passive"))
      (node (ref "U$2") (pin "U2") (pinfunction "1_U2") (pintype "bidirectional"))
    )
    (net (code "75") (name "Net-(U$2R-1)") (class "Default")
      (node (ref "D14") (pin "A") (pinfunction "A_A") (pintype "passive"))
      (node (ref "D21") (pin "A") (pinfunction "A_A") (pintype "passive"))
      (node (ref "D28") (pin "A") (pinfunction "A_A") (pintype "passive"))
      (node (ref "D7") (pin "A") (pinfunction "A_A") (pintype "passive"))
      (node (ref "U$2") (pin "V2") (pinfunction "1_V2") (pintype "bidirectional"))
    )
    (net (code "76") (name "VCC") (class "Default")
      (node (ref "R11") (pin "2") (pinfunction "2_2") (pintype "passive"))
      (node (ref "R17") (pin "2") (pinfunction "2_2") (pintype "passive"))
      (node (ref "R23") (pin "2") (pinfunction "2_2") (pintype "passive"))
      (node (ref "R5") (pin "2") (pinfunction "2_2") (pintype "passive"))
      (node (ref "U$2") (pin "A2") (pinfunction "1_A2") (pintype "bidirectional"))
    )
  )
)
